# Gondola_Sail_electronics_M4.net
KiCad netlist of a schematic drawn in EAGLE
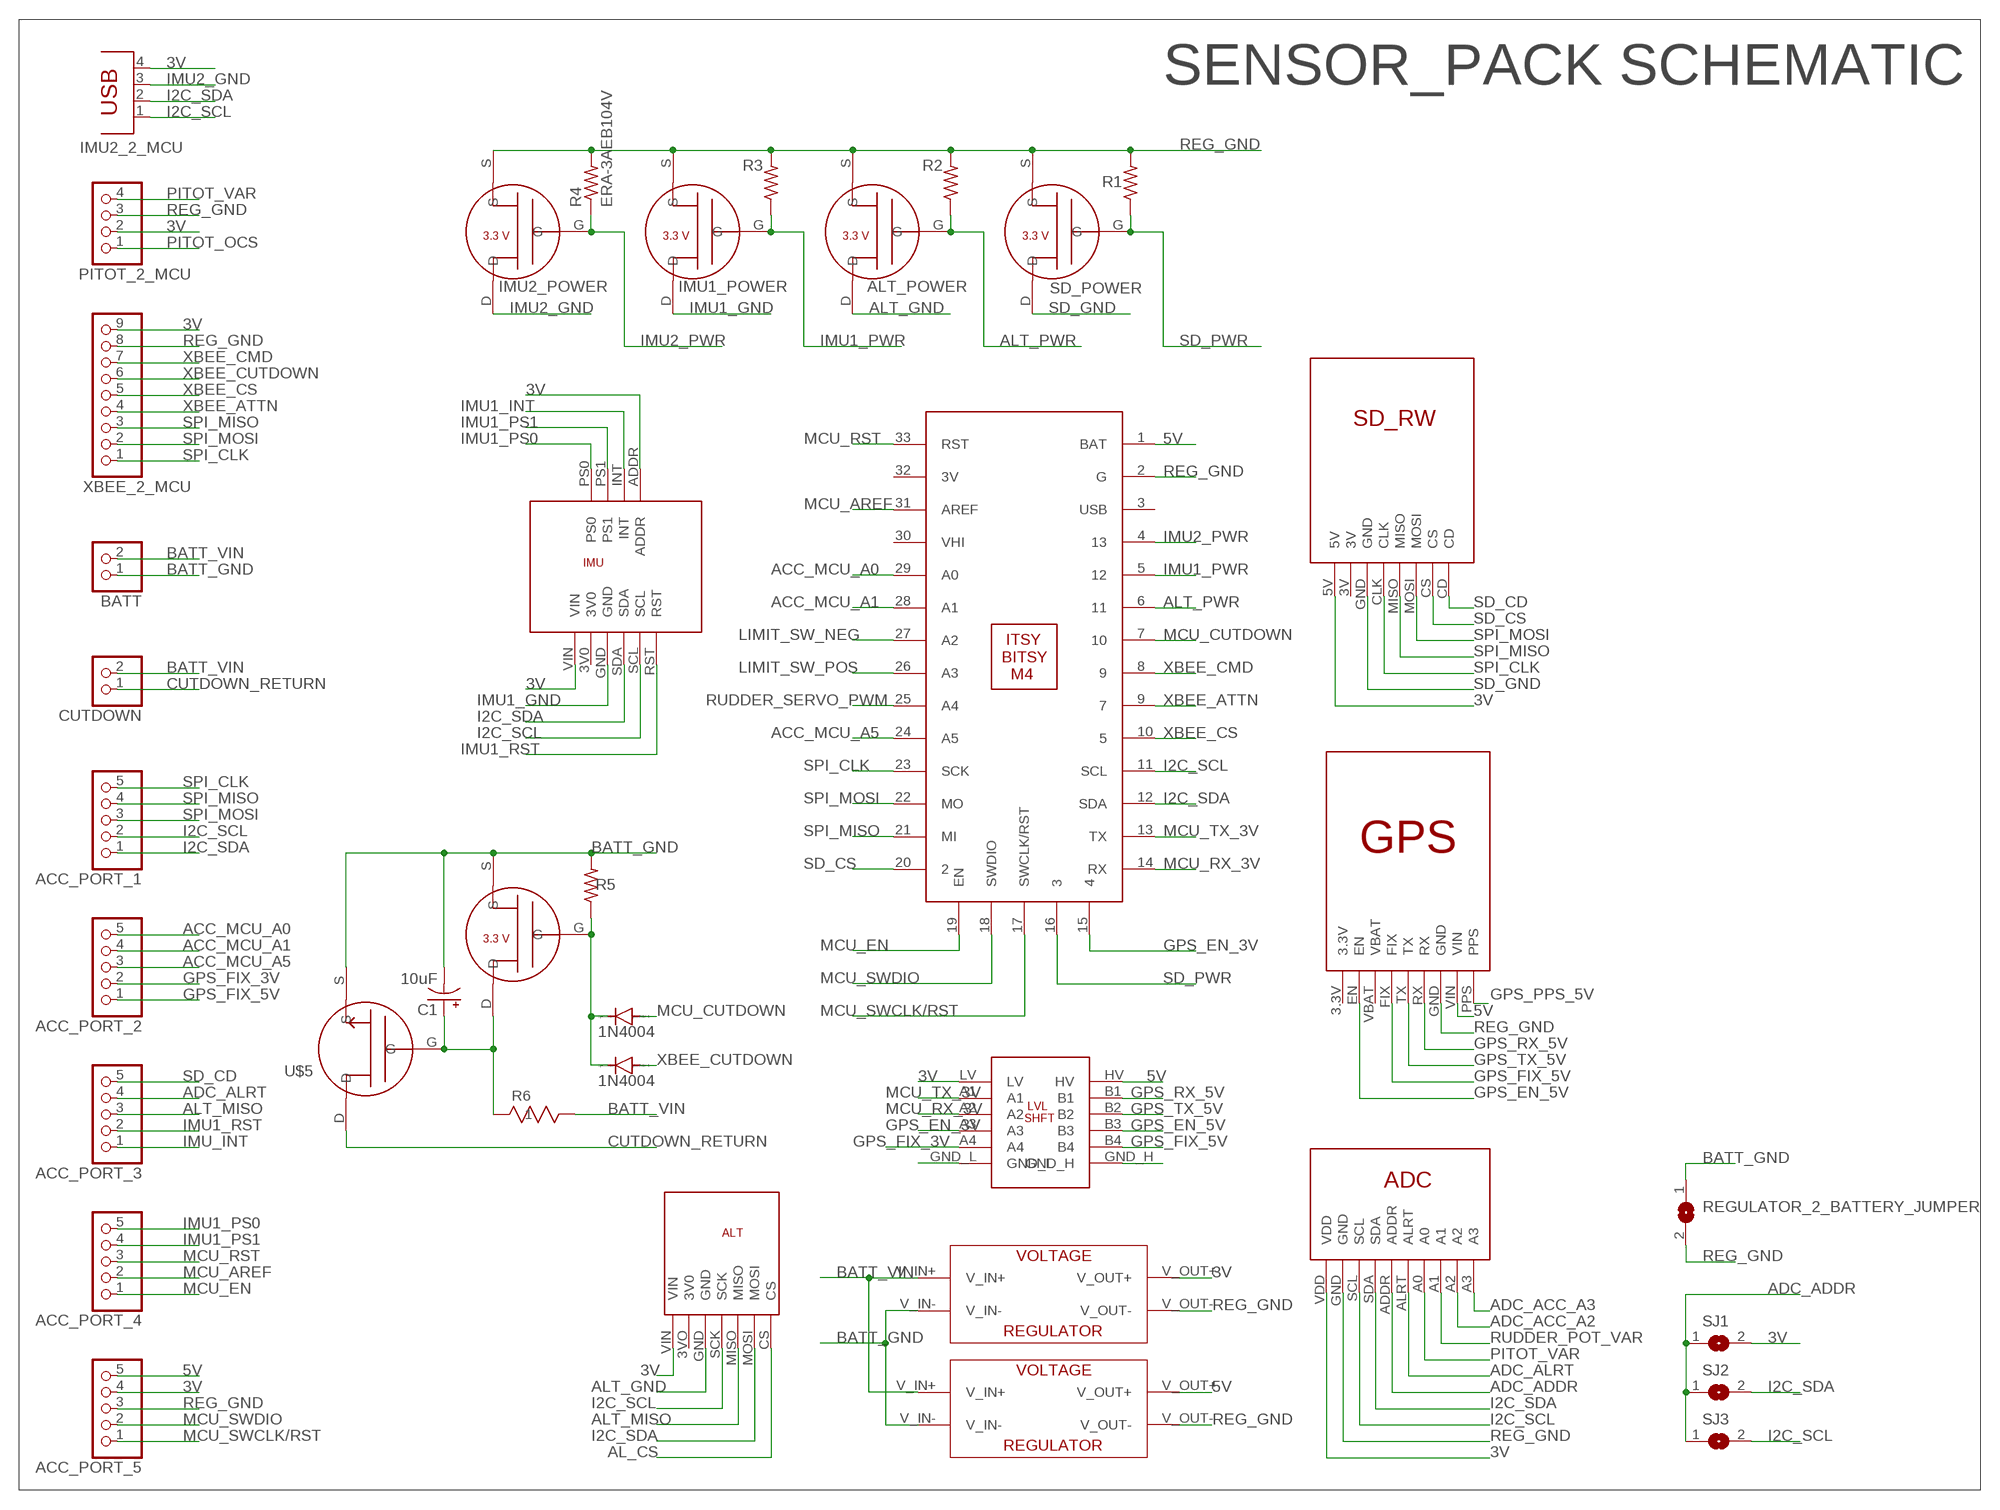
[diagram p0: schematic, sheet 1]

(export (version "E")
  (design (tool "Eeschema 10.0.6"))
  (components
    (comp (ref "3V_REG")
      (value "3V/5V_REGULATOR")
      (footprint "eagle-import:5V_3V_REGULATOR")
      (libsource (lib "eagle-import") (part "3V/5V_REGULATOR"))
    )
    (comp (ref "5V_REG")
      (value "3V/5V_REGULATOR")
      (footprint "eagle-import:5V_3V_REGULATOR")
      (libsource (lib "eagle-import") (part "3V/5V_REGULATOR"))
    )
    (comp (ref "ACC_PORT_1")
      (value "PINHD-1X5/90")
      (footprint "eagle-import:1X05_90")
      (libsource (lib "eagle-import") (part "PINHD-1X5/90"))
    )
    (comp (ref "ACC_PORT_2")
      (value "PINHD-1X5/90")
      (footprint "eagle-import:1X05_90")
      (libsource (lib "eagle-import") (part "PINHD-1X5/90"))
    )
    (comp (ref "ACC_PORT_3")
      (value "PINHD-1X5/90")
      (footprint "eagle-import:1X05_90")
      (libsource (lib "eagle-import") (part "PINHD-1X5/90"))
    )
    (comp (ref "ACC_PORT_4")
      (value "PINHD-1X5/90")
      (footprint "eagle-import:1X05_90")
      (libsource (lib "eagle-import") (part "PINHD-1X5/90"))
    )
    (comp (ref "ACC_PORT_5")
      (value "PINHD-1X5/90")
      (footprint "eagle-import:1X05_90")
      (libsource (lib "eagle-import") (part "PINHD-1X5/90"))
    )
    (comp (ref "ALT_POWER")
      (value "3.3V_NCH_FET")
      (footprint "eagle-import:3.3VTRANSISTOR")
      (libsource (lib "eagle-import") (part "3.3V_NCH_FET"))
    )
    (comp (ref "BATT")
      (value "PINHD-1X2/90")
      (footprint "eagle-import:1X02_90")
      (libsource (lib "eagle-import") (part "PINHD-1X2/90"))
    )
    (comp (ref "C1")
      (value "10uF")
      (footprint "eagle-import:CPOL-RADIAL-2.5MM-5MM")
      (libsource (lib "eagle-import") (part "10UF-POLAR-RADIAL-2.5MM-25V-20%"))
    )
    (comp (ref "CUTDOWN")
      (value "PINHD-1X2/90")
      (footprint "eagle-import:1X02_90")
      (libsource (lib "eagle-import") (part "PINHD-1X2/90"))
    )
    (comp (ref "D1")
      (value "1N4004")
      (footprint "eagle-import:DO41-10")
      (libsource (lib "eagle-import") (part "1N4004"))
    )
    (comp (ref "D2")
      (value "1N4004")
      (footprint "eagle-import:DO41-10")
      (libsource (lib "eagle-import") (part "1N4004"))
    )
    (comp (ref "IMU1")
      (value "BNO055")
      (footprint "eagle-import:BNO055")
      (libsource (lib "eagle-import") (part "BNO055"))
    )
    (comp (ref "IMU1_POWER")
      (value "3.3V_NCH_FET")
      (footprint "eagle-import:3.3VTRANSISTOR")
      (libsource (lib "eagle-import") (part "3.3V_NCH_FET"))
    )
    (comp (ref "IMU2_2_MCU")
      (value "PN87520")
      (footprint "eagle-import:PN87520")
      (libsource (lib "eagle-import") (part "PN87520"))
    )
    (comp (ref "IMU2_POWER")
      (value "3.3V_NCH_FET")
      (footprint "eagle-import:3.3VTRANSISTOR")
      (libsource (lib "eagle-import") (part "3.3V_NCH_FET"))
    )
    (comp (ref "PITOT_2_MCU")
      (value "PINHD-1X4/90")
      (footprint "eagle-import:1X04_90")
      (libsource (lib "eagle-import") (part "PINHD-1X4/90"))
    )
    (comp (ref "R1")
      (value "ERA-3AEB104V")
      (footprint "eagle-import:RESC1608X55")
      (fields (field (name "DIGI-KEY_PART_NUMBER") "P100KDBCT-ND") (field (name "MF") "Panasonic"))
      (libsource (lib "eagle-import") (part "ERA-3AEB104V"))
    )
    (comp (ref "R2")
      (value "ERA-3AEB104V")
      (footprint "eagle-import:RESC1608X55")
      (fields (field (name "DIGI-KEY_PART_NUMBER") "P100KDBCT-ND") (field (name "MF") "Panasonic"))
      (libsource (lib "eagle-import") (part "ERA-3AEB104V"))
    )
    (comp (ref "R3")
      (value "ERA-3AEB104V")
      (footprint "eagle-import:RESC1608X55")
      (fields (field (name "DIGI-KEY_PART_NUMBER") "P100KDBCT-ND") (field (name "MF") "Panasonic"))
      (libsource (lib "eagle-import") (part "ERA-3AEB104V"))
    )
    (comp (ref "R4")
      (value "ERA-3AEB104V")
      (footprint "eagle-import:RESC1608X55")
      (fields (field (name "DIGI-KEY_PART_NUMBER") "P100KDBCT-ND") (field (name "MF") "Panasonic"))
      (libsource (lib "eagle-import") (part "ERA-3AEB104V"))
    )
    (comp (ref "R5")
      (value "ERA-3AEB104V")
      (footprint "eagle-import:RESC1608X55")
      (fields (field (name "DIGI-KEY_PART_NUMBER") "P100KDBCT-ND") (field (name "MF") "Panasonic"))
      (libsource (lib "eagle-import") (part "ERA-3AEB104V"))
    )
    (comp (ref "R6")
      (value "RR0816P-103-D")
      (footprint "eagle-import:RES_0816")
      (fields (field (name "MANUFACTURER_PART_NUMBER") "RR0816P103D"))
      (libsource (lib "eagle-import") (part "RR0816P-103-D"))
    )
    (comp (ref "REGULATOR_2_BATTERY_JUMPER")
      (value "SJW")
      (footprint "eagle-import:SJW")
      (libsource (lib "eagle-import") (part "SJW"))
    )
    (comp (ref "SD_POWER")
      (value "3.3V_NCH_FET")
      (footprint "eagle-import:3.3VTRANSISTOR")
      (libsource (lib "eagle-import") (part "3.3V_NCH_FET"))
    )
    (comp (ref "SD_POWER1")
      (value "3.3V_NCH_FET")
      (footprint "eagle-import:3.3VTRANSISTOR")
      (libsource (lib "eagle-import") (part "3.3V_NCH_FET"))
    )
    (comp (ref "SJ1") (value "SJ") (footprint "eagle-import:SJ") (libsource (lib "eagle-import") (part "SJ")))
    (comp (ref "SJ2") (value "SJ") (footprint "eagle-import:SJ") (libsource (lib "eagle-import") (part "SJ")))
    (comp (ref "SJ3") (value "SJ") (footprint "eagle-import:SJ") (libsource (lib "eagle-import") (part "SJ")))
    (comp (ref "U$1")
      (value "ADAFRUIT_GPS")
      (footprint "eagle-import:ADAFRUIT_GPS")
      (libsource (lib "eagle-import") (part "ADAFRUIT_GPS"))
    )
    (comp (ref "U$2")
      (value "ADAFRUI_SD_RW")
      (footprint "eagle-import:ADAFRUIT_SD_RW")
      (libsource (lib "eagle-import") (part "ADAFRUI_SD_RW"))
    )
    (comp (ref "U$3")
      (value "ADS1115")
      (footprint "eagle-import:ADS1115")
      (libsource (lib "eagle-import") (part "ADS1115"))
    )
    (comp (ref "U$4")
      (value "BME280")
      (footprint "eagle-import:BME280")
      (libsource (lib "eagle-import") (part "BME280"))
    )
    (comp (ref "U$5")
      (value "CUTDOWN_POWER_TRANSISTOR")
      (footprint "eagle-import:T03B")
      (libsource (lib "eagle-import") (part "CUTDOWN_POWER_TRANSISTOR"))
    )
    (comp (ref "U$6")
      (value "BSS138_LVLSHIFT")
      (footprint "eagle-import:BSS138_LEVELSHIFT")
      (libsource (lib "eagle-import") (part "BSS138_LVLSHIFT"))
    )
    (comp (ref "U$8")
      (value "ITSY_BITSY_M4")
      (footprint "eagle-import:ITSY_BITSY_M4")
      (libsource (lib "eagle-import") (part "ITSY_BITSY_M4"))
    )
    (comp (ref "XBEE_2_MCU")
      (value "PINHD-1X9/90")
      (footprint "eagle-import:1X09_90")
      (libsource (lib "eagle-import") (part "PINHD-1X9/90"))
    )
  )
  (nets
    (net (code "1") (name "/3V") (class "Default")
      (node (ref "3V_REG") (pin "V_OUT+") (pinfunction "V_OUT+_V_OUT+") (pintype "bidirectional"))
      (node (ref "ACC_PORT_5") (pin "4") (pinfunction "4_4") (pintype "passive"))
      (node (ref "IMU1") (pin "ADDR") (pinfunction "ADDR_ADDR") (pintype "bidirectional"))
      (node (ref "IMU1") (pin "VIN") (pinfunction "VIN_VIN") (pintype "bidirectional"))
      (node (ref "IMU2_2_MCU") (pin "4") (pinfunction "4_4") (pintype "passive"))
      (node (ref "PITOT_2_MCU") (pin "2") (pinfunction "2_2") (pintype "passive"))
      (node (ref "SJ1") (pin "2") (pinfunction "2_2") (pintype "passive"))
      (node (ref "U$2") (pin "5V") (pinfunction "5V_5V") (pintype "bidirectional"))
      (node (ref "U$3") (pin "VDD") (pinfunction "VDD_VDD") (pintype "bidirectional"))
      (node (ref "U$4") (pin "VIN") (pinfunction "VIN_VIN") (pintype "bidirectional"))
      (node (ref "U$6") (pin "LV") (pinfunction "LV_LV") (pintype "bidirectional"))
      (node (ref "XBEE_2_MCU") (pin "9") (pinfunction "9_9") (pintype "passive"))
    )
    (net (code "2") (name "/5V") (class "Default")
      (node (ref "5V_REG") (pin "V_OUT+") (pinfunction "V_OUT+_V_OUT+") (pintype "bidirectional"))
      (node (ref "ACC_PORT_5") (pin "5") (pinfunction "5_5") (pintype "passive"))
      (node (ref "U$1") (pin "VIN") (pinfunction "VIN_VIN") (pintype "bidirectional"))
      (node (ref "U$6") (pin "HV") (pinfunction "HV_HV") (pintype "bidirectional"))
      (node (ref "U$8") (pin "1") (pinfunction "BAT_1") (pintype "output"))
    )
    (net (code "3") (name "/ACC_MCU_A0") (class "Default")
      (node (ref "ACC_PORT_2") (pin "5") (pinfunction "5_5") (pintype "passive"))
      (node (ref "U$8") (pin "29") (pinfunction "A0_29") (pintype "bidirectional"))
    )
    (net (code "4") (name "/ACC_MCU_A1") (class "Default")
      (node (ref "ACC_PORT_2") (pin "4") (pinfunction "4_4") (pintype "passive"))
      (node (ref "U$8") (pin "28") (pinfunction "A1_28") (pintype "bidirectional"))
    )
    (net (code "5") (name "/ACC_MCU_A5") (class "Default")
      (node (ref "ACC_PORT_2") (pin "3") (pinfunction "3_3") (pintype "passive"))
      (node (ref "U$8") (pin "24") (pinfunction "A5_24") (pintype "bidirectional"))
    )
    (net (code "6") (name "/ADC_ACC_A2") (class "Default")
      (node (ref "U$3") (pin "A2") (pinfunction "A2_A2") (pintype "bidirectional"))
    )
    (net (code "7") (name "/ADC_ACC_A3") (class "Default")
      (node (ref "U$3") (pin "A3") (pinfunction "A3_A3") (pintype "bidirectional"))
    )
    (net (code "8") (name "/ADC_ADDR") (class "Default")
      (node (ref "SJ1") (pin "1") (pinfunction "1_1") (pintype "passive"))
      (node (ref "SJ2") (pin "1") (pinfunction "1_1") (pintype "passive"))
      (node (ref "SJ3") (pin "1") (pinfunction "1_1") (pintype "passive"))
      (node (ref "U$3") (pin "ADDR") (pinfunction "ADDR_ADDR") (pintype "bidirectional"))
    )
    (net (code "9") (name "/ADC_ALRT") (class "Default")
      (node (ref "ACC_PORT_3") (pin "4") (pinfunction "4_4") (pintype "passive"))
      (node (ref "U$3") (pin "ALRT") (pinfunction "ALRT_ALRT") (pintype "bidirectional"))
    )
    (net (code "10") (name "/ALT_GND") (class "Default")
      (node (ref "ALT_POWER") (pin "D") (pinfunction "D_D") (pintype "bidirectional"))
      (node (ref "U$4") (pin "GND") (pinfunction "GND_GND") (pintype "bidirectional"))
    )
    (net (code "11") (name "/ALT_MISO") (class "Default")
      (node (ref "ACC_PORT_3") (pin "3") (pinfunction "3_3") (pintype "passive"))
      (node (ref "U$4") (pin "MISO") (pinfunction "MISO_MISO") (pintype "bidirectional"))
    )
    (net (code "12") (name "/ALT_PWR") (class "Default")
      (node (ref "ALT_POWER") (pin "G") (pinfunction "G_G") (pintype "bidirectional"))
      (node (ref "R2") (pin "1") (pinfunction "1_1") (pintype "passive"))
      (node (ref "U$8") (pin "6") (pinfunction "11_6") (pintype "bidirectional"))
    )
    (net (code "13") (name "/AL_CS") (class "Default")
      (node (ref "U$4") (pin "CS") (pinfunction "CS_CS") (pintype "bidirectional"))
    )
    (net (code "14") (name "/BATT_GND") (class "Default")
      (node (ref "3V_REG") (pin "V_IN-") (pinfunction "V_IN-_V_IN-") (pintype "bidirectional"))
      (node (ref "5V_REG") (pin "V_IN-") (pinfunction "V_IN-_V_IN-") (pintype "bidirectional"))
      (node (ref "BATT") (pin "1") (pinfunction "1_1") (pintype "passive"))
      (node (ref "C1") (pin "2") (pinfunction "-_2") (pintype "passive"))
      (node (ref "R5") (pin "2") (pinfunction "2_2") (pintype "passive"))
      (node (ref "REGULATOR_2_BATTERY_JUMPER") (pin "1") (pinfunction "1_1") (pintype "passive"))
      (node (ref "SD_POWER1") (pin "S") (pinfunction "S_S") (pintype "bidirectional"))
      (node (ref "U$5") (pin "S") (pinfunction "S_S") (pintype "bidirectional"))
    )
    (net (code "15") (name "/BATT_VIN") (class "Default")
      (node (ref "3V_REG") (pin "V_IN+") (pinfunction "V_IN+_V_IN+") (pintype "bidirectional"))
      (node (ref "5V_REG") (pin "V_IN+") (pinfunction "V_IN+_V_IN+") (pintype "bidirectional"))
      (node (ref "BATT") (pin "2") (pinfunction "2_2") (pintype "passive"))
      (node (ref "CUTDOWN") (pin "2") (pinfunction "2_2") (pintype "passive"))
      (node (ref "R6") (pin "2") (pinfunction "2_2") (pintype "passive"))
    )
    (net (code "16") (name "/CUTDOWN_RETURN") (class "Default")
      (node (ref "CUTDOWN") (pin "1") (pinfunction "1_1") (pintype "passive"))
      (node (ref "U$5") (pin "D") (pinfunction "D_D") (pintype "bidirectional"))
    )
    (net (code "17") (name "/GPS_EN_3V") (class "Default")
      (node (ref "U$6") (pin "A3") (pinfunction "A3_A3") (pintype "bidirectional"))
      (node (ref "U$8") (pin "15") (pinfunction "4_15") (pintype "bidirectional"))
    )
    (net (code "18") (name "/GPS_EN_5V") (class "Default")
      (node (ref "U$1") (pin "EN") (pinfunction "EN_EN") (pintype "bidirectional"))
      (node (ref "U$6") (pin "B3") (pinfunction "B3_B3") (pintype "bidirectional"))
    )
    (net (code "19") (name "/GPS_FIX_3V") (class "Default")
      (node (ref "ACC_PORT_2") (pin "2") (pinfunction "2_2") (pintype "passive"))
      (node (ref "U$6") (pin "A4") (pinfunction "A4_A4") (pintype "bidirectional"))
    )
    (net (code "20") (name "/GPS_FIX_5V") (class "Default")
      (node (ref "ACC_PORT_2") (pin "1") (pinfunction "1_1") (pintype "passive"))
      (node (ref "U$1") (pin "FIX") (pinfunction "FIX_FIX") (pintype "bidirectional"))
      (node (ref "U$6") (pin "B4") (pinfunction "B4_B4") (pintype "bidirectional"))
    )
    (net (code "21") (name "/GPS_PPS_5V") (class "Default")
      (node (ref "U$1") (pin "PPS") (pinfunction "PPS_PPS") (pintype "bidirectional"))
    )
    (net (code "22") (name "/GPS_RX_5V") (class "Default")
      (node (ref "U$1") (pin "RX") (pinfunction "RX_RX") (pintype "bidirectional"))
      (node (ref "U$6") (pin "B1") (pinfunction "B1_B1") (pintype "bidirectional"))
    )
    (net (code "23") (name "/GPS_TX_5V") (class "Default")
      (node (ref "U$1") (pin "TX") (pinfunction "TX_TX") (pintype "bidirectional"))
      (node (ref "U$6") (pin "B2") (pinfunction "B2_B2") (pintype "bidirectional"))
    )
    (net (code "24") (name "/I2C_SCL") (class "Default")
      (node (ref "ACC_PORT_1") (pin "2") (pinfunction "2_2") (pintype "passive"))
      (node (ref "IMU1") (pin "SCL") (pinfunction "SCL_SCL") (pintype "bidirectional"))
      (node (ref "IMU2_2_MCU") (pin "1") (pinfunction "1_1") (pintype "passive"))
      (node (ref "SJ3") (pin "2") (pinfunction "2_2") (pintype "passive"))
      (node (ref "U$3") (pin "SCL") (pinfunction "SCL_SCL") (pintype "bidirectional"))
      (node (ref "U$4") (pin "SCK") (pinfunction "SCK_SCK") (pintype "bidirectional"))
      (node (ref "U$8") (pin "11") (pinfunction "SCL_11") (pintype "bidirectional"))
    )
    (net (code "25") (name "/I2C_SDA") (class "Default")
      (node (ref "ACC_PORT_1") (pin "1") (pinfunction "1_1") (pintype "passive"))
      (node (ref "IMU1") (pin "SDA") (pinfunction "SDA_SDA") (pintype "bidirectional"))
      (node (ref "IMU2_2_MCU") (pin "2") (pinfunction "2_2") (pintype "passive"))
      (node (ref "SJ2") (pin "2") (pinfunction "2_2") (pintype "passive"))
      (node (ref "U$3") (pin "SDA") (pinfunction "SDA_SDA") (pintype "bidirectional"))
      (node (ref "U$4") (pin "MOSI") (pinfunction "MOSI_MOSI") (pintype "bidirectional"))
      (node (ref "U$8") (pin "12") (pinfunction "SDA_12") (pintype "bidirectional"))
    )
    (net (code "26") (name "/IMU1_GND") (class "Default")
      (node (ref "IMU1") (pin "GND") (pinfunction "GND_GND") (pintype "bidirectional"))
      (node (ref "IMU1_POWER") (pin "D") (pinfunction "D_D") (pintype "bidirectional"))
    )
    (net (code "27") (name "/IMU1_INT") (class "Default")
      (node (ref "IMU1") (pin "INT") (pinfunction "INT_INT") (pintype "bidirectional"))
    )
    (net (code "28") (name "/IMU1_PS0") (class "Default")
      (node (ref "ACC_PORT_4") (pin "5") (pinfunction "5_5") (pintype "passive"))
      (node (ref "IMU1") (pin "PS0") (pinfunction "PS0_PS0") (pintype "bidirectional"))
    )
    (net (code "29") (name "/IMU1_PS1") (class "Default")
      (node (ref "ACC_PORT_4") (pin "4") (pinfunction "4_4") (pintype "passive"))
      (node (ref "IMU1") (pin "PS1") (pinfunction "PS1_PS1") (pintype "bidirectional"))
    )
    (net (code "30") (name "/IMU1_PWR") (class "Default")
      (node (ref "IMU1_POWER") (pin "G") (pinfunction "G_G") (pintype "bidirectional"))
      (node (ref "R3") (pin "1") (pinfunction "1_1") (pintype "passive"))
      (node (ref "U$8") (pin "5") (pinfunction "12_5") (pintype "bidirectional"))
    )
    (net (code "31") (name "/IMU1_RST") (class "Default")
      (node (ref "ACC_PORT_3") (pin "2") (pinfunction "2_2") (pintype "passive"))
      (node (ref "IMU1") (pin "RST") (pinfunction "RST_RST") (pintype "bidirectional"))
    )
    (net (code "32") (name "/IMU2_GND") (class "Default")
      (node (ref "IMU2_2_MCU") (pin "3") (pinfunction "3_3") (pintype "passive"))
      (node (ref "IMU2_POWER") (pin "D") (pinfunction "D_D") (pintype "bidirectional"))
    )
    (net (code "33") (name "/IMU2_PWR") (class "Default")
      (node (ref "IMU2_POWER") (pin "G") (pinfunction "G_G") (pintype "bidirectional"))
      (node (ref "R4") (pin "1") (pinfunction "1_1") (pintype "passive"))
      (node (ref "U$8") (pin "4") (pinfunction "13_4") (pintype "bidirectional"))
    )
    (net (code "34") (name "/IMU_INT") (class "Default")
      (node (ref "ACC_PORT_3") (pin "1") (pinfunction "1_1") (pintype "passive"))
    )
    (net (code "35") (name "/LIMIT_SW_NEG") (class "Default")
      (node (ref "U$8") (pin "27") (pinfunction "A2_27") (pintype "bidirectional"))
    )
    (net (code "36") (name "/LIMIT_SW_POS") (class "Default")
      (node (ref "U$8") (pin "26") (pinfunction "A3_26") (pintype "bidirectional"))
    )
    (net (code "37") (name "/MCU_AREF") (class "Default")
      (node (ref "ACC_PORT_4") (pin "2") (pinfunction "2_2") (pintype "passive"))
      (node (ref "U$8") (pin "31") (pinfunction "AREF_31") (pintype "bidirectional"))
    )
    (net (code "38") (name "/MCU_CUTDOWN") (class "Default")
      (node (ref "D1") (pin "A") (pinfunction "A_A") (pintype "passive"))
      (node (ref "U$8") (pin "7") (pinfunction "10_7") (pintype "bidirectional"))
    )
    (net (code "39") (name "/MCU_EN") (class "Default")
      (node (ref "ACC_PORT_4") (pin "1") (pinfunction "1_1") (pintype "passive"))
      (node (ref "U$8") (pin "19") (pinfunction "EN_19") (pintype "bidirectional"))
    )
    (net (code "40") (name "/MCU_RST") (class "Default")
      (node (ref "ACC_PORT_4") (pin "3") (pinfunction "3_3") (pintype "passive"))
      (node (ref "U$8") (pin "33") (pinfunction "RST_33") (pintype "bidirectional"))
    )
    (net (code "41") (name "/MCU_RX_3V") (class "Default")
      (node (ref "U$6") (pin "A2") (pinfunction "A2_A2") (pintype "bidirectional"))
      (node (ref "U$8") (pin "14") (pinfunction "RX_14") (pintype "bidirectional"))
    )
    (net (code "42") (name "/MCU_SWCLK{slash}RST") (class "Default")
      (node (ref "ACC_PORT_5") (pin "1") (pinfunction "1_1") (pintype "passive"))
      (node (ref "U$8") (pin "17") (pinfunction "SWCLK/RST_17") (pintype "bidirectional"))
    )
    (net (code "43") (name "/MCU_SWDIO") (class "Default")
      (node (ref "ACC_PORT_5") (pin "2") (pinfunction "2_2") (pintype "passive"))
      (node (ref "U$8") (pin "18") (pinfunction "SWDIO_18") (pintype "bidirectional"))
    )
    (net (code "44") (name "/MCU_TX_3V") (class "Default")
      (node (ref "U$6") (pin "A1") (pinfunction "A1_A1") (pintype "bidirectional"))
      (node (ref "U$8") (pin "13") (pinfunction "TX_13") (pintype "bidirectional"))
    )
    (net (code "45") (name "/PITOT_OCS") (class "Default")
      (node (ref "PITOT_2_MCU") (pin "1") (pinfunction "1_1") (pintype "passive"))
    )
    (net (code "46") (name "/PITOT_VAR") (class "Default")
      (node (ref "PITOT_2_MCU") (pin "4") (pinfunction "4_4") (pintype "passive"))
      (node (ref "U$3") (pin "A0") (pinfunction "A0_A0") (pintype "bidirectional"))
    )
    (net (code "47") (name "/REG_GND") (class "Default")
      (node (ref "3V_REG") (pin "V_OUT-") (pinfunction "V_OUT-_V_OUT-") (pintype "bidirectional"))
      (node (ref "5V_REG") (pin "V_OUT-") (pinfunction "V_OUT-_V_OUT-") (pintype "bidirectional"))
      (node (ref "ACC_PORT_5") (pin "3") (pinfunction "3_3") (pintype "passive"))
      (node (ref "ALT_POWER") (pin "S") (pinfunction "S_S") (pintype "bidirectional"))
      (node (ref "IMU1_POWER") (pin "S") (pinfunction "S_S") (pintype "bidirectional"))
      (node (ref "IMU2_POWER") (pin "S") (pinfunction "S_S") (pintype "bidirectional"))
      (node (ref "PITOT_2_MCU") (pin "3") (pinfunction "3_3") (pintype "passive"))
      (node (ref "R1") (pin "2") (pinfunction "2_2") (pintype "passive"))
      (node (ref "R2") (pin "2") (pinfunction "2_2") (pintype "passive"))
      (node (ref "R3") (pin "2") (pinfunction "2_2") (pintype "passive"))
      (node (ref "R4") (pin "2") (pinfunction "2_2") (pintype "passive"))
      (node (ref "REGULATOR_2_BATTERY_JUMPER") (pin "2") (pinfunction "2_2") (pintype "passive"))
      (node (ref "SD_POWER") (pin "S") (pinfunction "S_S") (pintype "bidirectional"))
      (node (ref "U$1") (pin "GND") (pinfunction "GND_GND") (pintype "bidirectional"))
      (node (ref "U$3") (pin "GND") (pinfunction "GND_GND") (pintype "bidirectional"))
      (node (ref "U$8") (pin "2") (pinfunction "G_2") (pintype "bidirectional"))
      (node (ref "XBEE_2_MCU") (pin "8") (pinfunction "8_8") (pintype "passive"))
    )
    (net (code "48") (name "/RUDDER_POT_VAR") (class "Default")
      (node (ref "U$3") (pin "A1") (pinfunction "A1_A1") (pintype "bidirectional"))
    )
    (net (code "49") (name "/RUDDER_SERVO_PWM") (class "Default")
      (node (ref "U$8") (pin "25") (pinfunction "A4_25") (pintype "bidirectional"))
    )
    (net (code "50") (name "/SD_CD") (class "Default")
      (node (ref "ACC_PORT_3") (pin "5") (pinfunction "5_5") (pintype "passive"))
      (node (ref "U$2") (pin "CD") (pinfunction "CD_CD") (pintype "bidirectional"))
    )
    (net (code "51") (name "/SD_CS") (class "Default")
      (node (ref "U$2") (pin "CS") (pinfunction "CS_CS") (pintype "bidirectional"))
      (node (ref "U$8") (pin "20") (pinfunction "2_20") (pintype "bidirectional"))
    )
    (net (code "52") (name "/SD_GND") (class "Default")
      (node (ref "SD_POWER") (pin "D") (pinfunction "D_D") (pintype "bidirectional"))
      (node (ref "U$2") (pin "GND") (pinfunction "GND_GND") (pintype "bidirectional"))
    )
    (net (code "53") (name "/SD_PWR") (class "Default")
      (node (ref "R1") (pin "1") (pinfunction "1_1") (pintype "passive"))
      (node (ref "SD_POWER") (pin "G") (pinfunction "G_G") (pintype "bidirectional"))
      (node (ref "U$8") (pin "16") (pinfunction "3_16") (pintype "bidirectional"))
    )
    (net (code "54") (name "/SPI_CLK") (class "Default")
      (node (ref "ACC_PORT_1") (pin "5") (pinfunction "5_5") (pintype "passive"))
      (node (ref "U$2") (pin "CLK") (pinfunction "CLK_CLK") (pintype "bidirectional"))
      (node (ref "U$8") (pin "23") (pinfunction "SCK_23") (pintype "bidirectional"))
      (node (ref "XBEE_2_MCU") (pin "1") (pinfunction "1_1") (pintype "passive"))
    )
    (net (code "55") (name "/SPI_MISO") (class "Default")
      (node (ref "ACC_PORT_1") (pin "4") (pinfunction "4_4") (pintype "passive"))
      (node (ref "U$2") (pin "MISO") (pinfunction "MISO_MISO") (pintype "bidirectional"))
      (node (ref "U$8") (pin "21") (pinfunction "MI_21") (pintype "bidirectional"))
      (node (ref "XBEE_2_MCU") (pin "3") (pinfunction "3_3") (pintype "passive"))
    )
    (net (code "56") (name "/SPI_MOSI") (class "Default")
      (node (ref "ACC_PORT_1") (pin "3") (pinfunction "3_3") (pintype "passive"))
      (node (ref "U$2") (pin "MOSI") (pinfunction "MOSI_MOSI") (pintype "bidirectional"))
      (node (ref "U$8") (pin "22") (pinfunction "MO_22") (pintype "bidirectional"))
      (node (ref "XBEE_2_MCU") (pin "2") (pinfunction "2_2") (pintype "passive"))
    )
    (net (code "57") (name "/XBEE_ATTN") (class "Default")
      (node (ref "U$8") (pin "9") (pinfunction "7_9") (pintype "bidirectional"))
      (node (ref "XBEE_2_MCU") (pin "4") (pinfunction "4_4") (pintype "passive"))
    )
    (net (code "58") (name "/XBEE_CMD") (class "Default")
      (node (ref "U$8") (pin "8") (pinfunction "9_8") (pintype "bidirectional"))
      (node (ref "XBEE_2_MCU") (pin "7") (pinfunction "7_7") (pintype "passive"))
    )
    (net (code "59") (name "/XBEE_CS") (class "Default")
      (node (ref "U$8") (pin "10") (pinfunction "5_10") (pintype "bidirectional"))
      (node (ref "XBEE_2_MCU") (pin "5") (pinfunction "5_5") (pintype "passive"))
    )
    (net (code "60") (name "/XBEE_CUTDOWN") (class "Default")
      (node (ref "D2") (pin "A") (pinfunction "A_A") (pintype "passive"))
      (node (ref "XBEE_2_MCU") (pin "6") (pinfunction "6_6") (pintype "passive"))
    )
    (net (code "61") (name "Net-(C1-+)") (class "Default")
      (node (ref "C1") (pin "1") (pinfunction "+_1") (pintype "passive"))
      (node (ref "R6") (pin "1") (pinfunction "1_1") (pintype "passive"))
      (node (ref "SD_POWER1") (pin "D") (pinfunction "D_D") (pintype "bidirectional"))
      (node (ref "U$5") (pin "G") (pinfunction "G_G") (pintype "bidirectional"))
    )
    (net (code "62") (name "Net-(D1-PadC)") (class "Default")
      (node (ref "D1") (pin "C") (pinfunction "C_C") (pintype "passive"))
      (node (ref "D2") (pin "C") (pinfunction "C_C") (pintype "passive"))
      (node (ref "R5") (pin "1") (pinfunction "1_1") (pintype "passive"))
      (node (ref "SD_POWER1") (pin "G") (pinfunction "G_G") (pintype "bidirectional"))
    )
    (net (code "63") (name "unconnected-(IMU1-Pad3V0)") (class "Default")
      (node (ref "IMU1") (pin "3V0") (pinfunction "3V0_3V0") (pintype "bidirectional"))
    )
    (net (code "64") (name "unconnected-(U$1-Pad3.3V)") (class "Default")
      (node (ref "U$1") (pin "3.3V") (pinfunction "3.3V_3.3V") (pintype "bidirectional"))
    )
    (net (code "65") (name "unconnected-(U$1-PadVBAT)") (class "Default")
      (node (ref "U$1") (pin "VBAT") (pinfunction "VBAT_VBAT") (pintype "bidirectional"))
    )
    (net (code "66") (name "unconnected-(U$2-Pad3V)") (class "Default")
      (node (ref "U$2") (pin "3V") (pinfunction "3V_3V") (pintype "bidirectional"))
    )
    (net (code "67") (name "unconnected-(U$4-3V0-Pad3VO)") (class "Default")
      (node (ref "U$4") (pin "3VO") (pinfunction "3V0_3VO") (pintype "bidirectional"))
    )
    (net (code "68") (name "unconnected-(U$6-PadGND_H)") (class "Default")
      (node (ref "U$6") (pin "GND_H") (pinfunction "GND_H_GND_H") (pintype "bidirectional"))
    )
    (net (code "69") (name "unconnected-(U$6-PadGND_L)") (class "Default")
      (node (ref "U$6") (pin "GND_L") (pinfunction "GND_L_GND_L") (pintype "bidirectional"))
    )
    (net (code "70") (name "unconnected-(U$8-3V-Pad32)") (class "Default")
      (node (ref "U$8") (pin "32") (pinfunction "3V_32") (pintype "bidirectional"))
    )
    (net (code "71") (name "unconnected-(U$8-USB-Pad3)") (class "Default")
      (node (ref "U$8") (pin "3") (pinfunction "USB_3") (pintype "bidirectional"))
    )
    (net (code "72") (name "unconnected-(U$8-VHI-Pad30)") (class "Default")
      (node (ref "U$8") (pin "30") (pinfunction "VHI_30") (pintype "bidirectional"))
    )
  )
)
